# ByrneLite.net
KiCad netlist of a schematic drawn in EAGLE
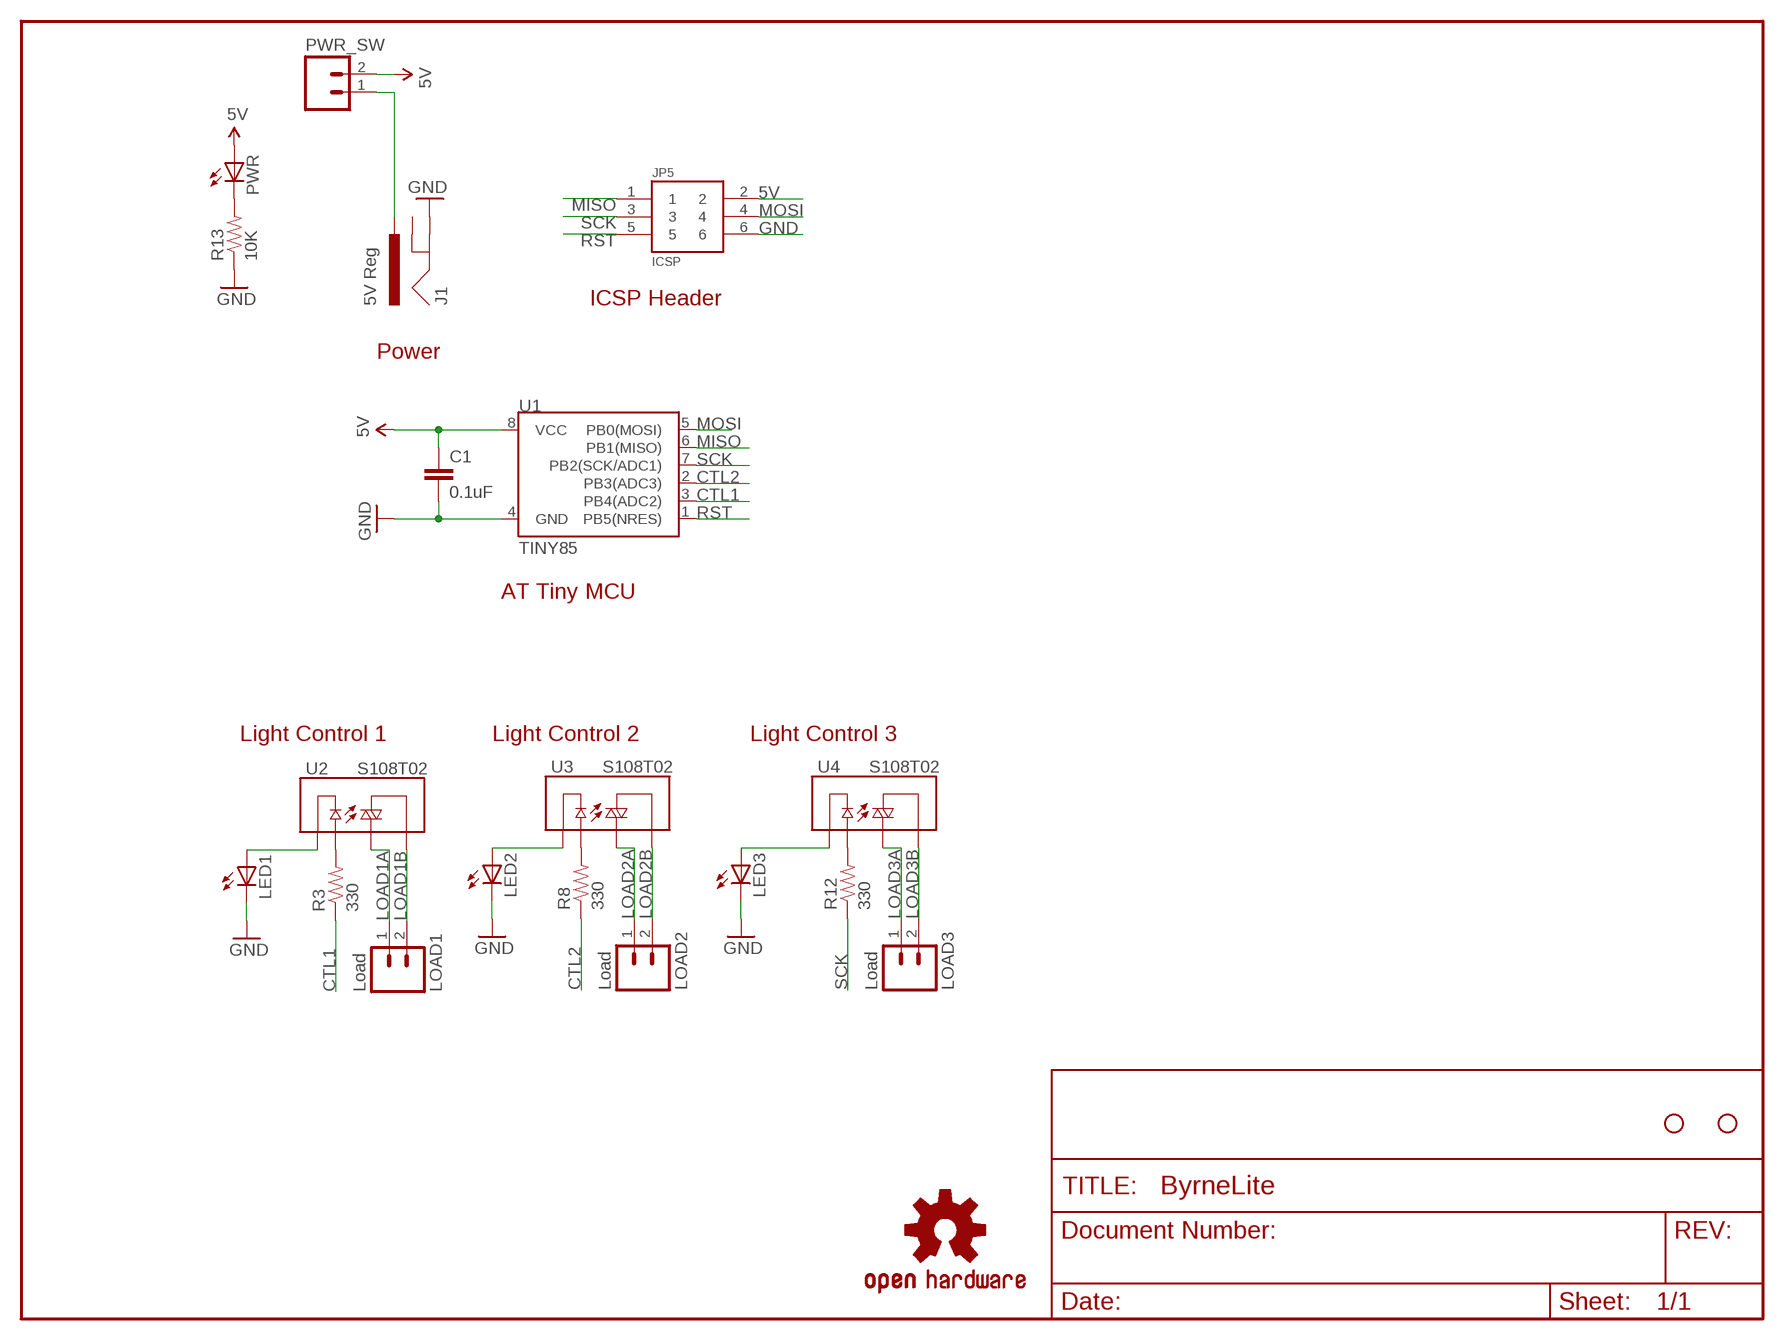
[diagram p0: schematic, sheet 1]

(export (version "E")
  (design (tool "Eeschema 10.0.6"))
  (components
    (comp (ref "C1")
      (value "0.1uF")
      (footprint "eagle-import:CAP-PTH-SMALL2")
      (libsource (lib "eagle-import") (part "CAPPTH2"))
    )
    (comp (ref "J1")
      (value "5V Reg")
      (footprint "eagle-import:POWER_JACK_PTH_LOCK")
      (libsource (lib "eagle-import") (part "POWER_JACKPTH_LOCK"))
    )
    (comp (ref "JP5")
      (value "ICSP")
      (footprint "eagle-import:2X3-SHROUDED")
      (libsource (lib "eagle-import") (part "M03X2"))
    )
    (comp (ref "LED1")
      (value "LED5MM")
      (footprint "eagle-import:LED5MM")
      (libsource (lib "eagle-import") (part "LED5MM"))
    )
    (comp (ref "LED2")
      (value "LED5MM")
      (footprint "eagle-import:LED5MM")
      (libsource (lib "eagle-import") (part "LED5MM"))
    )
    (comp (ref "LED3")
      (value "LED5MM")
      (footprint "eagle-import:LED5MM")
      (libsource (lib "eagle-import") (part "LED5MM"))
    )
    (comp (ref "LOAD1")
      (value "Load")
      (footprint "eagle-import:SCREWTERMINAL-5MM-2")
      (libsource (lib "eagle-import") (part "M025MM"))
    )
    (comp (ref "LOAD2")
      (value "Load")
      (footprint "eagle-import:SCREWTERMINAL-5MM-2")
      (libsource (lib "eagle-import") (part "M025MM"))
    )
    (comp (ref "LOAD3")
      (value "Load")
      (footprint "eagle-import:SCREWTERMINAL-5MM-2")
      (libsource (lib "eagle-import") (part "M025MM"))
    )
    (comp (ref "LOGO1")
      (value "OSHW-LOGOM")
      (footprint "eagle-import:OSHW-LOGO-M")
      (libsource (lib "eagle-import") (part "OSHW-LOGOM"))
    )
    (comp (ref "PWR")
      (value "LED3MM")
      (footprint "eagle-import:LED3MM")
      (libsource (lib "eagle-import") (part "LED3MM"))
    )
    (comp (ref "PWR_SW")
      (value "M02PTH3")
      (footprint "eagle-import:1X02_LONGPADS")
      (libsource (lib "eagle-import") (part "SparkFun-Connectors_M02PTH3"))
    )
    (comp (ref "R3")
      (value "330")
      (footprint "eagle-import:AXIAL-0.3")
      (libsource (lib "eagle-import") (part "RESISTORAXIAL-0.3"))
    )
    (comp (ref "R8")
      (value "330")
      (footprint "eagle-import:AXIAL-0.3")
      (libsource (lib "eagle-import") (part "RESISTORAXIAL-0.3"))
    )
    (comp (ref "R12")
      (value "330")
      (footprint "eagle-import:AXIAL-0.3")
      (libsource (lib "eagle-import") (part "RESISTORAXIAL-0.3"))
    )
    (comp (ref "R13")
      (value "10K")
      (footprint "eagle-import:AXIAL-0.3")
      (libsource (lib "eagle-import") (part "RESISTORAXIAL-0.3"))
    )
    (comp (ref "STANDOFF2")
      (value "STAND-OFF")
      (footprint "eagle-import:STAND-OFF")
      (libsource (lib "eagle-import") (part "STAND-OFF"))
    )
    (comp (ref "STANDOFF4")
      (value "STAND-OFF")
      (footprint "eagle-import:STAND-OFF")
      (libsource (lib "eagle-import") (part "STAND-OFF"))
    )
    (comp (ref "U1")
      (value "TINY85")
      (footprint "eagle-import:DIP08")
      (fields (field (name "PROD_ID") "IC-09445"))
      (libsource (lib "eagle-import") (part "ATTINY45TINY85-20-DIP"))
    )
    (comp (ref "U2")
      (value "S108T02")
      (footprint "eagle-import:RELAY-S108T02")
      (libsource (lib "eagle-import") (part "RELAY-SOLIDSTATEPTH"))
    )
    (comp (ref "U3")
      (value "S108T02")
      (footprint "eagle-import:RELAY-S108T02")
      (libsource (lib "eagle-import") (part "RELAY-SOLIDSTATEPTH"))
    )
    (comp (ref "U4")
      (value "S108T02")
      (footprint "eagle-import:RELAY-S108T02")
      (libsource (lib "eagle-import") (part "RELAY-SOLIDSTATEPTH"))
    )
  )
  (nets
    (net (code "1") (name "/CTL1") (class "Default")
      (node (ref "R3") (pin "P$1") (pinfunction "1_P$1") (pintype "passive"))
      (node (ref "U1") (pin "3") (pinfunction "PB4(ADC2)_3") (pintype "bidirectional"))
    )
    (net (code "2") (name "/CTL2") (class "Default")
      (node (ref "R8") (pin "P$1") (pinfunction "1_P$1") (pintype "passive"))
      (node (ref "U1") (pin "2") (pinfunction "PB3(ADC3)_2") (pintype "bidirectional"))
    )
    (net (code "3") (name "/LOAD1A") (class "Default")
      (node (ref "LOAD1") (pin "1") (pinfunction "1_1") (pintype "passive"))
      (node (ref "U2") (pin "2") (pinfunction "T2_2") (pintype "bidirectional"))
    )
    (net (code "4") (name "/LOAD1B") (class "Default")
      (node (ref "LOAD1") (pin "2") (pinfunction "2_2") (pintype "passive"))
      (node (ref "U2") (pin "1") (pinfunction "T1_1") (pintype "bidirectional"))
    )
    (net (code "5") (name "/LOAD2A") (class "Default")
      (node (ref "LOAD2") (pin "1") (pinfunction "1_1") (pintype "passive"))
      (node (ref "U3") (pin "2") (pinfunction "T2_2") (pintype "bidirectional"))
    )
    (net (code "6") (name "/LOAD2B") (class "Default")
      (node (ref "LOAD2") (pin "2") (pinfunction "2_2") (pintype "passive"))
      (node (ref "U3") (pin "1") (pinfunction "T1_1") (pintype "bidirectional"))
    )
    (net (code "7") (name "/LOAD3A") (class "Default")
      (node (ref "LOAD3") (pin "1") (pinfunction "1_1") (pintype "passive"))
      (node (ref "U4") (pin "2") (pinfunction "T2_2") (pintype "bidirectional"))
    )
    (net (code "8") (name "/LOAD3B") (class "Default")
      (node (ref "LOAD3") (pin "2") (pinfunction "2_2") (pintype "passive"))
      (node (ref "U4") (pin "1") (pinfunction "T1_1") (pintype "bidirectional"))
    )
    (net (code "9") (name "/MISO") (class "Default")
      (node (ref "JP5") (pin "1") (pinfunction "1_1") (pintype "bidirectional"))
      (node (ref "U1") (pin "6") (pinfunction "PB1(MISO)_6") (pintype "bidirectional"))
    )
    (net (code "10") (name "/MOSI") (class "Default")
      (node (ref "JP5") (pin "4") (pinfunction "4_4") (pintype "bidirectional"))
      (node (ref "U1") (pin "5") (pinfunction "PB0(MOSI)_5") (pintype "bidirectional"))
    )
    (net (code "11") (name "/RST") (class "Default")
      (node (ref "JP5") (pin "5") (pinfunction "5_5") (pintype "bidirectional"))
      (node (ref "U1") (pin "1") (pinfunction "PB5(NRES)_1") (pintype "bidirectional"))
    )
    (net (code "12") (name "/SCK") (class "Default")
      (node (ref "JP5") (pin "3") (pinfunction "3_3") (pintype "bidirectional"))
      (node (ref "R12") (pin "P$1") (pinfunction "1_P$1") (pintype "passive"))
      (node (ref "U1") (pin "7") (pinfunction "PB2(SCK/ADC1)_7") (pintype "bidirectional"))
    )
    (net (code "13") (name "5V") (class "Default")
      (node (ref "C1") (pin "1") (pinfunction "1_1") (pintype "passive"))
      (node (ref "JP5") (pin "2") (pinfunction "2_2") (pintype "bidirectional"))
      (node (ref "PWR") (pin "A") (pinfunction "A_A") (pintype "passive"))
      (node (ref "PWR_SW") (pin "2") (pinfunction "2_2") (pintype "passive"))
      (node (ref "U1") (pin "8") (pinfunction "VCC_8") (pintype "bidirectional"))
    )
    (net (code "14") (name "GND") (class "Default")
      (node (ref "C1") (pin "2") (pinfunction "2_2") (pintype "passive"))
      (node (ref "J1") (pin "GND") (pinfunction "GND_GND") (pintype "bidirectional"))
      (node (ref "JP5") (pin "6") (pinfunction "6_6") (pintype "bidirectional"))
      (node (ref "LED1") (pin "K") (pinfunction "C_K") (pintype "passive"))
      (node (ref "LED2") (pin "K") (pinfunction "C_K") (pintype "passive"))
      (node (ref "LED3") (pin "K") (pinfunction "C_K") (pintype "passive"))
      (node (ref "R13") (pin "P$1") (pinfunction "1_P$1") (pintype "passive"))
      (node (ref "U1") (pin "4") (pinfunction "GND_4") (pintype "bidirectional"))
    )
    (net (code "15") (name "Net-(J1-PadPWR)") (class "Default")
      (node (ref "J1") (pin "PWR") (pinfunction "PWR_PWR") (pintype "bidirectional"))
      (node (ref "PWR_SW") (pin "1") (pinfunction "1_1") (pintype "passive"))
    )
    (net (code "16") (name "Net-(PWR-C)") (class "Default")
      (node (ref "PWR") (pin "K") (pinfunction "C_K") (pintype "passive"))
      (node (ref "R13") (pin "P$2") (pinfunction "2_P$2") (pintype "passive"))
    )
    (net (code "17") (name "Net-(R3-2)") (class "Default")
      (node (ref "R3") (pin "P$2") (pinfunction "2_P$2") (pintype "passive"))
      (node (ref "U2") (pin "3") (pinfunction "+_3") (pintype "bidirectional"))
    )
    (net (code "18") (name "Net-(R8-2)") (class "Default")
      (node (ref "R8") (pin "P$2") (pinfunction "2_P$2") (pintype "passive"))
      (node (ref "U3") (pin "3") (pinfunction "+_3") (pintype "bidirectional"))
    )
    (net (code "19") (name "Net-(R12-2)") (class "Default")
      (node (ref "R12") (pin "P$2") (pinfunction "2_P$2") (pintype "passive"))
      (node (ref "U4") (pin "3") (pinfunction "+_3") (pintype "bidirectional"))
    )
    (net (code "20") (name "Net-(U2--)") (class "Default")
      (node (ref "LED1") (pin "A") (pinfunction "A_A") (pintype "passive"))
      (node (ref "U2") (pin "4") (pinfunction "-_4") (pintype "bidirectional"))
    )
    (net (code "21") (name "Net-(U3--)") (class "Default")
      (node (ref "LED2") (pin "A") (pinfunction "A_A") (pintype "passive"))
      (node (ref "U3") (pin "4") (pinfunction "-_4") (pintype "bidirectional"))
    )
    (net (code "22") (name "Net-(U4--)") (class "Default")
      (node (ref "LED3") (pin "A") (pinfunction "A_A") (pintype "passive"))
      (node (ref "U4") (pin "4") (pinfunction "-_4") (pintype "bidirectional"))
    )
    (net (code "23") (name "unconnected-(J1-PadGNDBREAK)") (class "Default")
      (node (ref "J1") (pin "GNDBREAK") (pinfunction "GNDBREAK_GNDBREAK") (pintype "bidirectional"))
    )
  )
)
